# M785.net
KiCad netlist of a schematic drawn in EAGLE
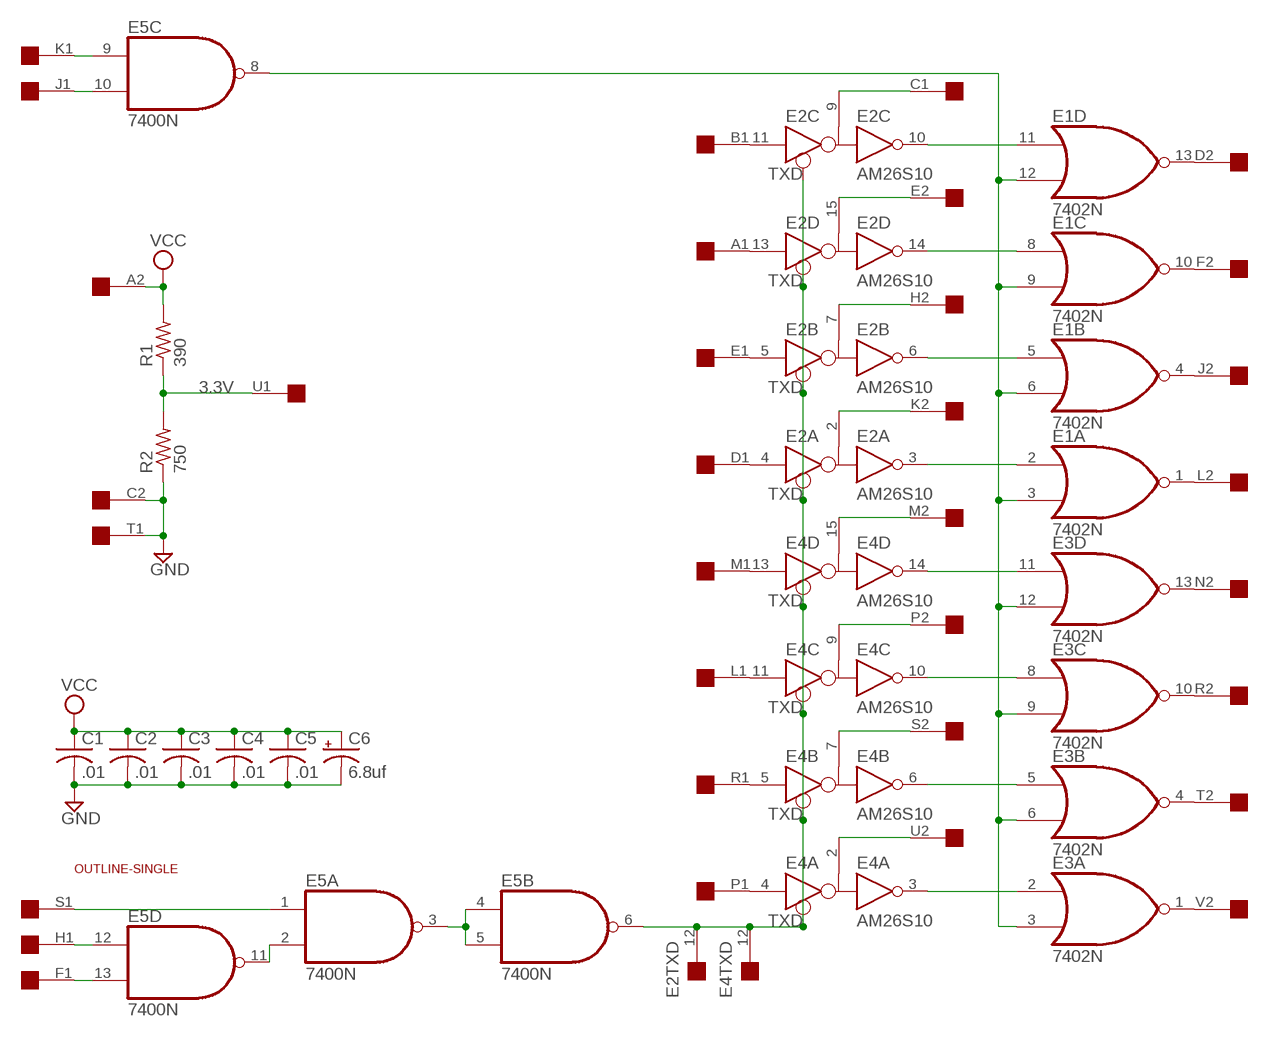
[diagram p0: schematic, sheet 1]

(export (version "E")
  (design (tool "Eeschema 10.0.6"))
  (components
    (comp (ref "C1")
      (value ".01")
      (footprint "eagle-import:C050-025X075")
      (libsource (lib "eagle-import") (part "C-US050-025X075"))
    )
    (comp (ref "C2")
      (value ".01")
      (footprint "eagle-import:C050-025X075")
      (libsource (lib "eagle-import") (part "C-US050-025X075"))
    )
    (comp (ref "C3")
      (value ".01")
      (footprint "eagle-import:C050-025X075")
      (libsource (lib "eagle-import") (part "C-US050-025X075"))
    )
    (comp (ref "C4")
      (value ".01")
      (footprint "eagle-import:C050-025X075")
      (libsource (lib "eagle-import") (part "C-US050-025X075"))
    )
    (comp (ref "C5")
      (value ".01")
      (footprint "eagle-import:C050-025X075")
      (libsource (lib "eagle-import") (part "C-US050-025X075"))
    )
    (comp (ref "C6")
      (value "6.8uf")
      (footprint "eagle-import:E15-5")
      (libsource (lib "eagle-import") (part "CPOL-USE15-5AXIAL"))
    )
    (comp (ref "E1")
      (value "7402N")
      (footprint "eagle-import:DIL14")
      (libsource (lib "eagle-import") (part "7402N"))
    )
    (comp (ref "E2")
      (value "AM26S10")
      (footprint "eagle-import:DIL16")
      (libsource (lib "eagle-import") (part "AM26S10"))
    )
    (comp (ref "E3")
      (value "7402N")
      (footprint "eagle-import:DIL14")
      (libsource (lib "eagle-import") (part "7402N"))
    )
    (comp (ref "E4")
      (value "AM26S10")
      (footprint "eagle-import:DIL16")
      (libsource (lib "eagle-import") (part "AM26S10"))
    )
    (comp (ref "E5")
      (value "7400N")
      (footprint "eagle-import:DIL14")
      (libsource (lib "eagle-import") (part "7400N"))
    )
    (comp (ref "R1")
      (value "390")
      (footprint "eagle-import:0207_10")
      (libsource (lib "eagle-import") (part "R-US_0207/10"))
    )
    (comp (ref "R2")
      (value "750")
      (footprint "eagle-import:0207_10")
      (libsource (lib "eagle-import") (part "R-US_0207/10"))
    )
    (comp (ref "U$1")
      (value "SINGLE")
      (footprint "eagle-import:EDGE-CON2")
      (libsource (lib "eagle-import") (part "SINGLE"))
    )
    (comp (ref "U$2")
      (value "OUTLINE-SINGLE")
      (footprint "eagle-import:SINGLE")
      (libsource (lib "eagle-import") (part "OUTLINE-SINGLE"))
    )
  )
  (nets
    (net (code "1") (name "/3.3V") (class "Default")
      (node (ref "R1") (pin "1") (pinfunction "1_1") (pintype "passive"))
      (node (ref "R2") (pin "2") (pinfunction "2_2") (pintype "passive"))
      (node (ref "U$1") (pin "U1") (pinfunction "1_U1") (pintype "bidirectional"))
    )
    (net (code "2") (name "GND") (class "Default")
      (node (ref "C1") (pin "2") (pinfunction "2_2") (pintype "passive"))
      (node (ref "C2") (pin "2") (pinfunction "2_2") (pintype "passive"))
      (node (ref "C3") (pin "2") (pinfunction "2_2") (pintype "passive"))
      (node (ref "C4") (pin "2") (pinfunction "2_2") (pintype "passive"))
      (node (ref "C5") (pin "2") (pinfunction "2_2") (pintype "passive"))
      (node (ref "C6") (pin "-") (pinfunction "-_-") (pintype "passive"))
      (node (ref "R2") (pin "1") (pinfunction "1_1") (pintype "passive"))
      (node (ref "U$1") (pin "C2") (pinfunction "1_C2") (pintype "bidirectional"))
      (node (ref "U$1") (pin "T1") (pinfunction "1_T1") (pintype "bidirectional"))
    )
    (net (code "3") (name "Net-(E1A-I0)") (class "Default")
      (node (ref "E1") (pin "2") (pinfunction "I0_2") (pintype "input"))
      (node (ref "E2") (pin "3") (pinfunction "R_3") (pintype "output"))
    )
    (net (code "4") (name "Net-(E1A-I1)") (class "Default")
      (node (ref "E1") (pin "12") (pinfunction "I1_12") (pintype "input"))
      (node (ref "E1") (pin "3") (pinfunction "I1_3") (pintype "input"))
      (node (ref "E1") (pin "6") (pinfunction "I1_6") (pintype "input"))
      (node (ref "E1") (pin "9") (pinfunction "I1_9") (pintype "input"))
      (node (ref "E3") (pin "12") (pinfunction "I1_12") (pintype "input"))
      (node (ref "E3") (pin "3") (pinfunction "I1_3") (pintype "input"))
      (node (ref "E3") (pin "6") (pinfunction "I1_6") (pintype "input"))
      (node (ref "E3") (pin "9") (pinfunction "I1_9") (pintype "input"))
      (node (ref "E5") (pin "8") (pinfunction "O_8") (pintype "output"))
    )
    (net (code "5") (name "Net-(E1A-O)") (class "Default")
      (node (ref "E1") (pin "1") (pinfunction "O_1") (pintype "output"))
      (node (ref "U$1") (pin "L2") (pinfunction "1_L2") (pintype "bidirectional"))
    )
    (net (code "6") (name "Net-(E1B-I0)") (class "Default")
      (node (ref "E1") (pin "5") (pinfunction "I0_5") (pintype "input"))
      (node (ref "E2") (pin "6") (pinfunction "R_6") (pintype "output"))
    )
    (net (code "7") (name "Net-(E1B-O)") (class "Default")
      (node (ref "E1") (pin "4") (pinfunction "O_4") (pintype "output"))
      (node (ref "U$1") (pin "J2") (pinfunction "1_J2") (pintype "bidirectional"))
    )
    (net (code "8") (name "Net-(E1C-I0)") (class "Default")
      (node (ref "E1") (pin "8") (pinfunction "I0_8") (pintype "input"))
      (node (ref "E2") (pin "14") (pinfunction "R_14") (pintype "output"))
    )
    (net (code "9") (name "Net-(E1C-O)") (class "Default")
      (node (ref "E1") (pin "10") (pinfunction "O_10") (pintype "output"))
      (node (ref "U$1") (pin "F2") (pinfunction "1_F2") (pintype "bidirectional"))
    )
    (net (code "10") (name "Net-(E1D-I0)") (class "Default")
      (node (ref "E1") (pin "11") (pinfunction "I0_11") (pintype "input"))
      (node (ref "E2") (pin "10") (pinfunction "R_10") (pintype "output"))
    )
    (net (code "11") (name "Net-(E1D-O)") (class "Default")
      (node (ref "E1") (pin "13") (pinfunction "O_13") (pintype "output"))
      (node (ref "U$1") (pin "D2") (pinfunction "1_D2") (pintype "bidirectional"))
    )
    (net (code "12") (name "Net-(E2A-B)") (class "Default")
      (node (ref "E2") (pin "2") (pinfunction "B_2") (pintype "bidirectional"))
      (node (ref "U$1") (pin "K2") (pinfunction "1_K2") (pintype "bidirectional"))
    )
    (net (code "13") (name "Net-(E2A-D)") (class "Default")
      (node (ref "E2") (pin "4") (pinfunction "D_4") (pintype "input"))
      (node (ref "U$1") (pin "D1") (pinfunction "1_D1") (pintype "bidirectional"))
    )
    (net (code "14") (name "Net-(E2B-B)") (class "Default")
      (node (ref "E2") (pin "7") (pinfunction "B_7") (pintype "bidirectional"))
      (node (ref "U$1") (pin "H2") (pinfunction "1_H2") (pintype "bidirectional"))
    )
    (net (code "15") (name "Net-(E2B-D)") (class "Default")
      (node (ref "E2") (pin "5") (pinfunction "D_5") (pintype "input"))
      (node (ref "U$1") (pin "E1") (pinfunction "1_E1") (pintype "bidirectional"))
    )
    (net (code "16") (name "Net-(E2C-B)") (class "Default")
      (node (ref "E2") (pin "9") (pinfunction "B_9") (pintype "bidirectional"))
      (node (ref "U$1") (pin "C1") (pinfunction "1_C1") (pintype "bidirectional"))
    )
    (net (code "17") (name "Net-(E2C-D)") (class "Default")
      (node (ref "E2") (pin "11") (pinfunction "D_11") (pintype "input"))
      (node (ref "U$1") (pin "B1") (pinfunction "1_B1") (pintype "bidirectional"))
    )
    (net (code "18") (name "Net-(E2D-B)") (class "Default")
      (node (ref "E2") (pin "15") (pinfunction "B_15") (pintype "bidirectional"))
      (node (ref "U$1") (pin "E2") (pinfunction "1_E2") (pintype "bidirectional"))
    )
    (net (code "19") (name "Net-(E2D-D)") (class "Default")
      (node (ref "E2") (pin "13") (pinfunction "D_13") (pintype "input"))
      (node (ref "U$1") (pin "A1") (pinfunction "1_A1") (pintype "bidirectional"))
    )
    (net (code "20") (name "Net-(E2G-TXD)") (class "Default")
      (node (ref "E2") (pin "12") (pinfunction "TXD_12") (pintype "input"))
      (node (ref "E4") (pin "12") (pinfunction "TXD_12") (pintype "input"))
      (node (ref "E5") (pin "6") (pinfunction "O_6") (pintype "output"))
    )
    (net (code "21") (name "Net-(E3A-I0)") (class "Default")
      (node (ref "E3") (pin "2") (pinfunction "I0_2") (pintype "input"))
      (node (ref "E4") (pin "3") (pinfunction "R_3") (pintype "output"))
    )
    (net (code "22") (name "Net-(E3A-O)") (class "Default")
      (node (ref "E3") (pin "1") (pinfunction "O_1") (pintype "output"))
      (node (ref "U$1") (pin "V2") (pinfunction "1_V2") (pintype "bidirectional"))
    )
    (net (code "23") (name "Net-(E3B-I0)") (class "Default")
      (node (ref "E3") (pin "5") (pinfunction "I0_5") (pintype "input"))
      (node (ref "E4") (pin "6") (pinfunction "R_6") (pintype "output"))
    )
    (net (code "24") (name "Net-(E3B-O)") (class "Default")
      (node (ref "E3") (pin "4") (pinfunction "O_4") (pintype "output"))
      (node (ref "U$1") (pin "T2") (pinfunction "1_T2") (pintype "bidirectional"))
    )
    (net (code "25") (name "Net-(E3C-I0)") (class "Default")
      (node (ref "E3") (pin "8") (pinfunction "I0_8") (pintype "input"))
      (node (ref "E4") (pin "10") (pinfunction "R_10") (pintype "output"))
    )
    (net (code "26") (name "Net-(E3C-O)") (class "Default")
      (node (ref "E3") (pin "10") (pinfunction "O_10") (pintype "output"))
      (node (ref "U$1") (pin "R2") (pinfunction "1_R2") (pintype "bidirectional"))
    )
    (net (code "27") (name "Net-(E3D-I0)") (class "Default")
      (node (ref "E3") (pin "11") (pinfunction "I0_11") (pintype "input"))
      (node (ref "E4") (pin "14") (pinfunction "R_14") (pintype "output"))
    )
    (net (code "28") (name "Net-(E3D-O)") (class "Default")
      (node (ref "E3") (pin "13") (pinfunction "O_13") (pintype "output"))
      (node (ref "U$1") (pin "N2") (pinfunction "1_N2") (pintype "bidirectional"))
    )
    (net (code "29") (name "Net-(E4A-B)") (class "Default")
      (node (ref "E4") (pin "2") (pinfunction "B_2") (pintype "bidirectional"))
      (node (ref "U$1") (pin "U2") (pinfunction "1_U2") (pintype "bidirectional"))
    )
    (net (code "30") (name "Net-(E4A-D)") (class "Default")
      (node (ref "E4") (pin "4") (pinfunction "D_4") (pintype "input"))
      (node (ref "U$1") (pin "P1") (pinfunction "1_P1") (pintype "bidirectional"))
    )
    (net (code "31") (name "Net-(E4B-B)") (class "Default")
      (node (ref "E4") (pin "7") (pinfunction "B_7") (pintype "bidirectional"))
      (node (ref "U$1") (pin "S2") (pinfunction "1_S2") (pintype "bidirectional"))
    )
    (net (code "32") (name "Net-(E4B-D)") (class "Default")
      (node (ref "E4") (pin "5") (pinfunction "D_5") (pintype "input"))
      (node (ref "U$1") (pin "R1") (pinfunction "1_R1") (pintype "bidirectional"))
    )
    (net (code "33") (name "Net-(E4C-B)") (class "Default")
      (node (ref "E4") (pin "9") (pinfunction "B_9") (pintype "bidirectional"))
      (node (ref "U$1") (pin "P2") (pinfunction "1_P2") (pintype "bidirectional"))
    )
    (net (code "34") (name "Net-(E4C-D)") (class "Default")
      (node (ref "E4") (pin "11") (pinfunction "D_11") (pintype "input"))
      (node (ref "U$1") (pin "L1") (pinfunction "1_L1") (pintype "bidirectional"))
    )
    (net (code "35") (name "Net-(E4D-B)") (class "Default")
      (node (ref "E4") (pin "15") (pinfunction "B_15") (pintype "bidirectional"))
      (node (ref "U$1") (pin "M2") (pinfunction "1_M2") (pintype "bidirectional"))
    )
    (net (code "36") (name "Net-(E4D-D)") (class "Default")
      (node (ref "E4") (pin "13") (pinfunction "D_13") (pintype "input"))
      (node (ref "U$1") (pin "M1") (pinfunction "1_M1") (pintype "bidirectional"))
    )
    (net (code "37") (name "Net-(E5A-I0)") (class "Default")
      (node (ref "E5") (pin "1") (pinfunction "I0_1") (pintype "input"))
      (node (ref "U$1") (pin "S1") (pinfunction "1_S1") (pintype "bidirectional"))
    )
    (net (code "38") (name "Net-(E5A-I1)") (class "Default")
      (node (ref "E5") (pin "11") (pinfunction "O_11") (pintype "output"))
      (node (ref "E5") (pin "2") (pinfunction "I1_2") (pintype "input"))
    )
    (net (code "39") (name "Net-(E5A-O)") (class "Default")
      (node (ref "E5") (pin "3") (pinfunction "O_3") (pintype "output"))
      (node (ref "E5") (pin "4") (pinfunction "I0_4") (pintype "input"))
      (node (ref "E5") (pin "5") (pinfunction "I1_5") (pintype "input"))
    )
    (net (code "40") (name "Net-(E5C-I0)") (class "Default")
      (node (ref "E5") (pin "9") (pinfunction "I0_9") (pintype "input"))
      (node (ref "U$1") (pin "K1") (pinfunction "1_K1") (pintype "bidirectional"))
    )
    (net (code "41") (name "Net-(E5C-I1)") (class "Default")
      (node (ref "E5") (pin "10") (pinfunction "I1_10") (pintype "input"))
      (node (ref "U$1") (pin "J1") (pinfunction "1_J1") (pintype "bidirectional"))
    )
    (net (code "42") (name "Net-(E5D-I0)") (class "Default")
      (node (ref "E5") (pin "12") (pinfunction "I0_12") (pintype "input"))
      (node (ref "U$1") (pin "H1") (pinfunction "1_H1") (pintype "bidirectional"))
    )
    (net (code "43") (name "Net-(E5D-I1)") (class "Default")
      (node (ref "E5") (pin "13") (pinfunction "I1_13") (pintype "input"))
      (node (ref "U$1") (pin "F1") (pinfunction "1_F1") (pintype "bidirectional"))
    )
    (net (code "44") (name "VCC") (class "Default")
      (node (ref "C1") (pin "1") (pinfunction "1_1") (pintype "passive"))
      (node (ref "C2") (pin "1") (pinfunction "1_1") (pintype "passive"))
      (node (ref "C3") (pin "1") (pinfunction "1_1") (pintype "passive"))
      (node (ref "C4") (pin "1") (pinfunction "1_1") (pintype "passive"))
      (node (ref "C5") (pin "1") (pinfunction "1_1") (pintype "passive"))
      (node (ref "C6") (pin "+") (pinfunction "+_+") (pintype "passive"))
      (node (ref "R1") (pin "2") (pinfunction "2_2") (pintype "passive"))
      (node (ref "U$1") (pin "A2") (pinfunction "1_A2") (pintype "bidirectional"))
    )
  )
)
